# Proiect_TSC_v41.net
KiCad netlist of a schematic drawn in EAGLE
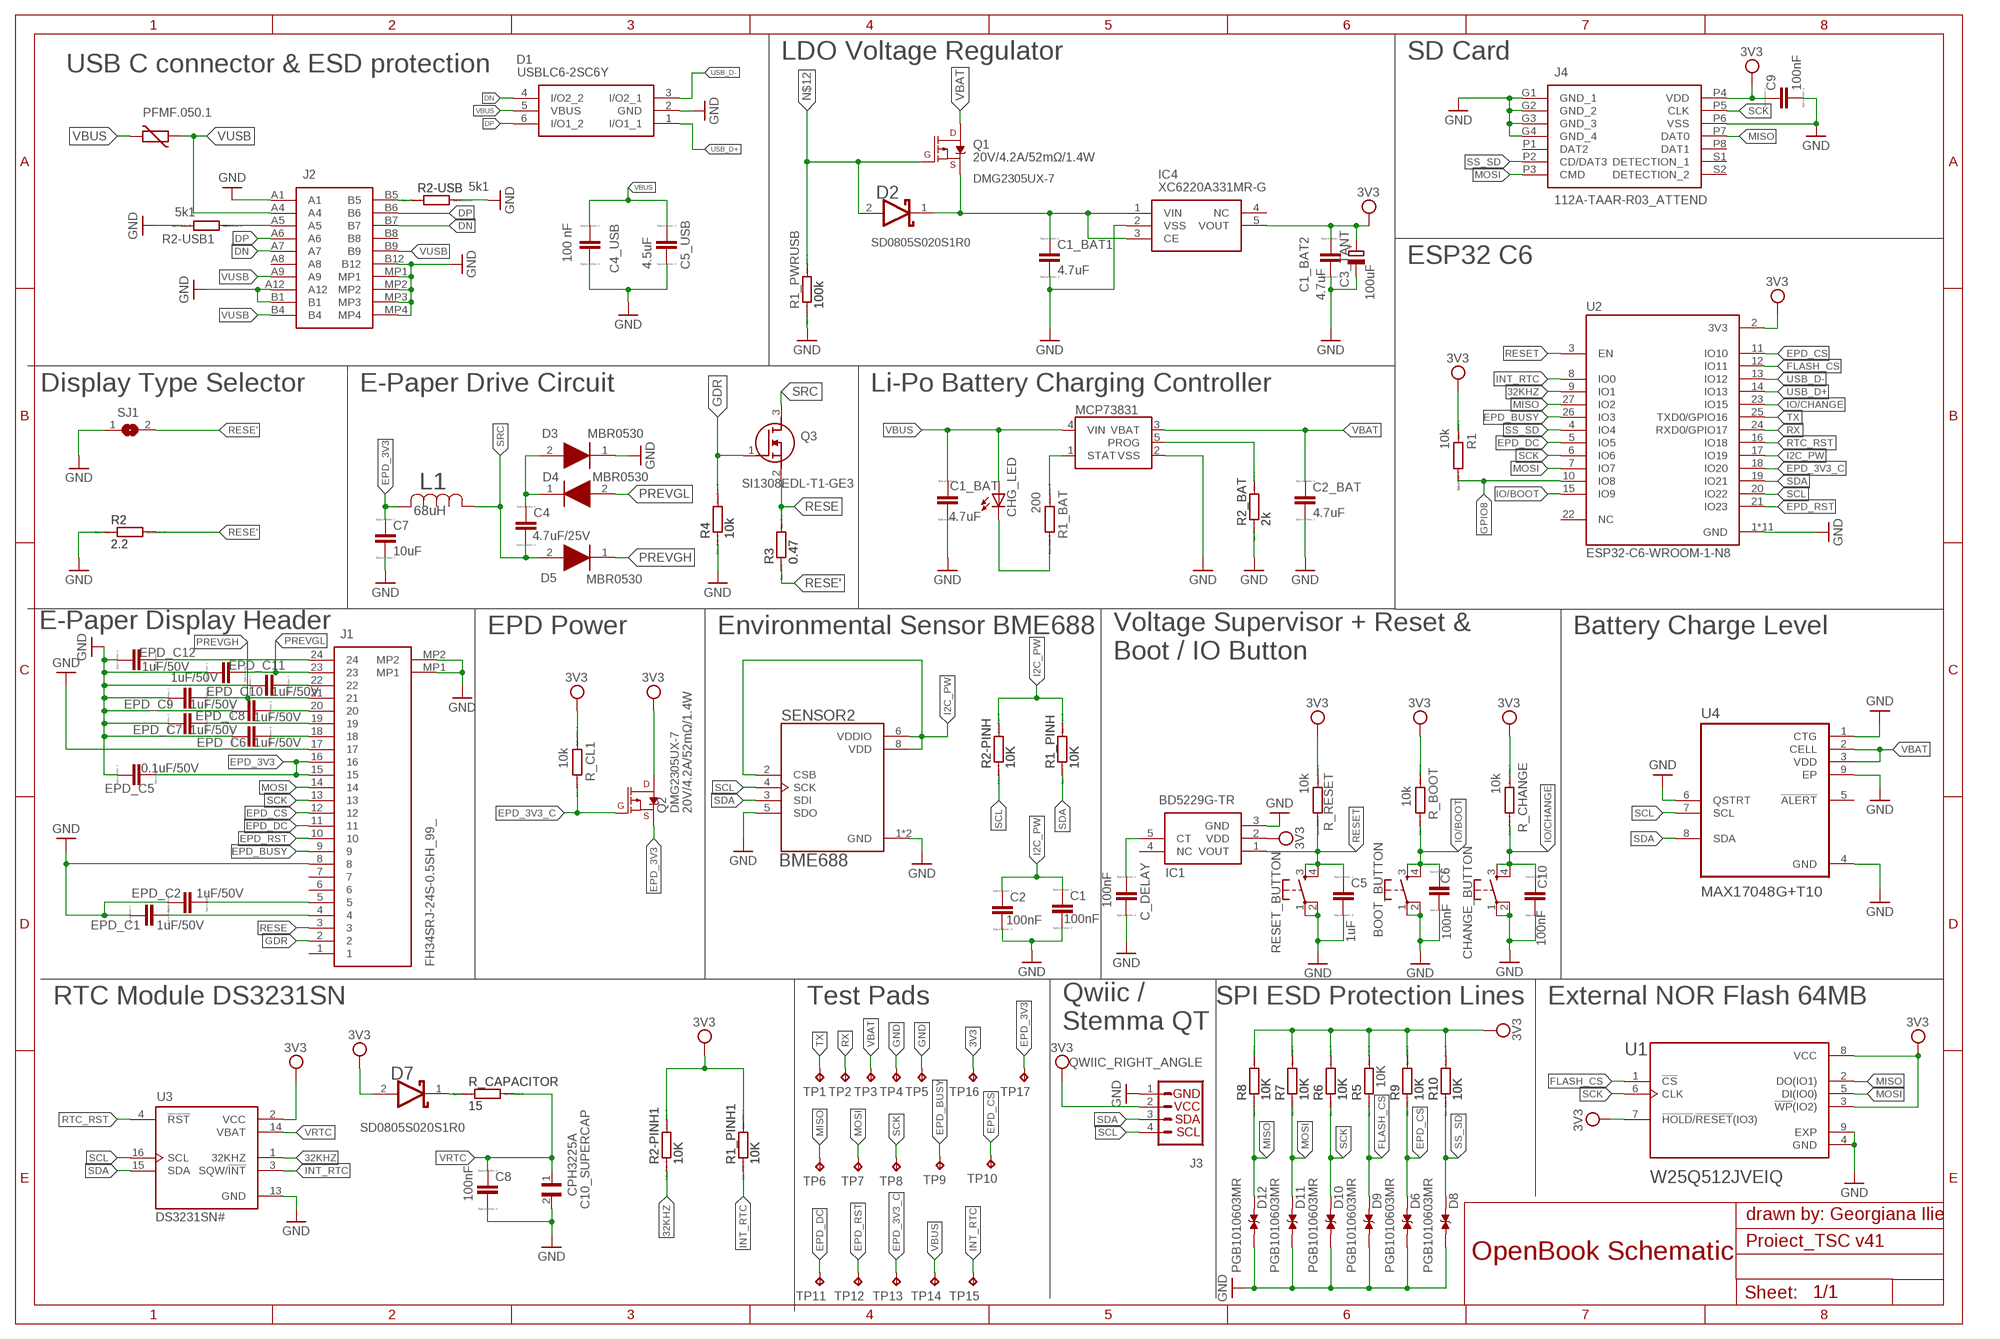
[diagram p0: schematic, sheet 1]

(export (version "E")
  (design (tool "Eeschema 10.0.6"))
  (components
    (comp (ref "BOOT_BUTTON")
      (value "BUTTON_CUSYOMV1")
      (footprint "eagle-import:MYBUTTON")
      (libsource (lib "eagle-import") (part "BUTTON_CUSYOMV1"))
    )
    (comp (ref "C1")
      (value "100nF")
      (footprint "eagle-import:EAGLE-LTSPICE_C0402")
      (libsource (lib "eagle-import") (part "EAGLE-LTSPICE_CC0402"))
    )
    (comp (ref "C1_BAT")
      (value "4.7uF")
      (footprint "eagle-import:EAGLE-LTSPICE_C0402")
      (libsource (lib "eagle-import") (part "EAGLE-LTSPICE_CC0402"))
    )
    (comp (ref "C1_BAT1")
      (value "4.7uF")
      (footprint "eagle-import:ESP32_WROVER_EAGLE-LTSPICE_C0402")
      (libsource (lib "eagle-import") (part "ESP32_WROVER_EAGLE-LTSPICE_CC0402"))
    )
    (comp (ref "C1_BAT2")
      (value "4.7uF")
      (footprint "eagle-import:ESP32_WROVER_EAGLE-LTSPICE_C0402")
      (libsource (lib "eagle-import") (part "ESP32_WROVER_EAGLE-LTSPICE_CC0402"))
    )
    (comp (ref "C2")
      (value "100nF")
      (footprint "eagle-import:EAGLE-LTSPICE_C0402")
      (libsource (lib "eagle-import") (part "EAGLE-LTSPICE_CC0402"))
    )
    (comp (ref "C2_BAT")
      (value "4.7uF")
      (footprint "eagle-import:EAGLE-LTSPICE_C0402")
      (libsource (lib "eagle-import") (part "EAGLE-LTSPICE_CC0402"))
    )
    (comp (ref "C3_TANT")
      (value "100uF")
      (footprint "eagle-import:RCL_CT3528")
      (libsource (lib "eagle-import") (part "RCL_CPOL-EUCT3528"))
    )
    (comp (ref "C4")
      (value "4.7uF/25V")
      (footprint "eagle-import:EAGLE-LTSPICE_C0402")
      (libsource (lib "eagle-import") (part "EAGLE-LTSPICE_CC0402"))
    )
    (comp (ref "C4_USB")
      (value "100 nF")
      (footprint "eagle-import:ESP32_WROVER_EAGLE-LTSPICE_C0402")
      (libsource (lib "eagle-import") (part "ESP32_WROVER_EAGLE-LTSPICE_CC0402"))
    )
    (comp (ref "C5")
      (value "1uF")
      (footprint "eagle-import:EAGLE-LTSPICE_C0402")
      (libsource (lib "eagle-import") (part "EAGLE-LTSPICE_CC0402"))
    )
    (comp (ref "C5_USB")
      (value "4.5uF")
      (footprint "eagle-import:ESP32_WROVER_EAGLE-LTSPICE_C0402")
      (libsource (lib "eagle-import") (part "ESP32_WROVER_EAGLE-LTSPICE_CC0402"))
    )
    (comp (ref "C6")
      (value "100nF")
      (footprint "eagle-import:EAGLE-LTSPICE_C0402")
      (libsource (lib "eagle-import") (part "EAGLE-LTSPICE_CC0402"))
    )
    (comp (ref "C7")
      (value "10uF")
      (footprint "eagle-import:EAGLE-LTSPICE_C0402")
      (libsource (lib "eagle-import") (part "EAGLE-LTSPICE_CC0402"))
    )
    (comp (ref "C8")
      (value "100nF")
      (footprint "eagle-import:EAGLE-LTSPICE_C0402")
      (libsource (lib "eagle-import") (part "EAGLE-LTSPICE_CC0402"))
    )
    (comp (ref "C9")
      (value "100nF")
      (footprint "eagle-import:EAGLE-LTSPICE_C0402")
      (libsource (lib "eagle-import") (part "EAGLE-LTSPICE_CC0402"))
    )
    (comp (ref "C10")
      (value "100nF")
      (footprint "eagle-import:EAGLE-LTSPICE_C0402")
      (libsource (lib "eagle-import") (part "EAGLE-LTSPICE_CC0402"))
    )
    (comp (ref "C10_SUPERCAP")
      (value "CPH3225A")
      (footprint "eagle-import:CAPCP3225X100N")
      (fields (field (name "MF") "Seiko Instruments"))
      (libsource (lib "eagle-import") (part "CPH3225A"))
    )
    (comp (ref "CHANGE_BUTTON")
      (value "BUTTON_CUSYOMV1")
      (footprint "eagle-import:MYBUTTON")
      (libsource (lib "eagle-import") (part "BUTTON_CUSYOMV1"))
    )
    (comp (ref "CHG_LED")
      (value "ADAFRUIT_LEDCHIP-LED0603")
      (footprint "eagle-import:ADAFRUIT_CHIP-LED0603")
      (libsource (lib "eagle-import") (part "ADAFRUIT_LEDCHIP-LED0603"))
    )
    (comp (ref "C_DELAY")
      (value "100nF")
      (footprint "eagle-import:EAGLE-LTSPICE_C0402")
      (libsource (lib "eagle-import") (part "EAGLE-LTSPICE_CC0402"))
    )
    (comp (ref "D1")
      (value "USBLC6-2SC6Y")
      (footprint "eagle-import:SOT95P280X145-6N")
      (fields (field (name "MF") "STMicroelectronics"))
      (libsource (lib "eagle-import") (part "USBLC6-2SC6Y"))
    )
    (comp (ref "D2")
      (value "ESP32_WROVER_AVX---SD0805S020S1R0_AVX_SD0805S020S1R0_0_0AVX_SD0805S020S1R0_0_0")
      (footprint "eagle-import:ESP32_WROVER_AVX---SD0805S020S1R0_AVX_SD0805S020S1R0_0")
      (fields
        (field (name "DIGIKEY_PART_NUMBER") "478-7800-1-ND")
        (field (name "MF") "AVX")
        (field (name "MOUSER_PART_NUMBER") "581-SD0805S020S1R0")
      )
      (libsource (lib "eagle-import") (part "ESP32_WROVER_AVX---SD0805S020S1R0_AVX_SD0805S020S1R0_0_0AVX_SD0805S020S1R0_0_0"))
    )
    (comp (ref "D3")
      (value "MBR0530")
      (footprint "eagle-import:SOD3716X135N")
      (fields (field (name "MF") "ON Semiconductor"))
      (libsource (lib "eagle-import") (part "MBR0530"))
    )
    (comp (ref "D4")
      (value "MBR0530")
      (footprint "eagle-import:SOD3716X135N")
      (fields (field (name "MF") "ON Semiconductor"))
      (libsource (lib "eagle-import") (part "MBR0530"))
    )
    (comp (ref "D5")
      (value "MBR0530")
      (footprint "eagle-import:SOD3716X135N")
      (fields (field (name "MF") "ON Semiconductor"))
      (libsource (lib "eagle-import") (part "MBR0530"))
    )
    (comp (ref "D6")
      (value "PGB1010603MR")
      (footprint "eagle-import:DIOC1608X36N")
      (fields (field (name "MF") "Littelfuse Inc."))
      (libsource (lib "eagle-import") (part "PGB1010603MR"))
    )
    (comp (ref "D7")
      (value "ESP32_WROVER_AVX---SD0805S020S1R0_AVX_SD0805S020S1R0_0_0AVX_SD0805S020S1R0_0_0")
      (footprint "eagle-import:ESP32_WROVER_AVX---SD0805S020S1R0_AVX_SD0805S020S1R0_0")
      (fields
        (field (name "DIGIKEY_PART_NUMBER") "478-7800-1-ND")
        (field (name "MF") "AVX")
        (field (name "MOUSER_PART_NUMBER") "581-SD0805S020S1R0")
      )
      (libsource (lib "eagle-import") (part "ESP32_WROVER_AVX---SD0805S020S1R0_AVX_SD0805S020S1R0_0_0AVX_SD0805S020S1R0_0_0"))
    )
    (comp (ref "D8")
      (value "PGB1010603MR")
      (footprint "eagle-import:DIOC1608X36N")
      (fields (field (name "MF") "Littelfuse Inc."))
      (libsource (lib "eagle-import") (part "PGB1010603MR"))
    )
    (comp (ref "D9")
      (value "PGB1010603MR")
      (footprint "eagle-import:DIOC1608X36N")
      (fields (field (name "MF") "Littelfuse Inc."))
      (libsource (lib "eagle-import") (part "PGB1010603MR"))
    )
    (comp (ref "D10")
      (value "PGB1010603MR")
      (footprint "eagle-import:DIOC1608X36N")
      (fields (field (name "MF") "Littelfuse Inc."))
      (libsource (lib "eagle-import") (part "PGB1010603MR"))
    )
    (comp (ref "D11")
      (value "PGB1010603MR")
      (footprint "eagle-import:DIOC1608X36N")
      (fields (field (name "MF") "Littelfuse Inc."))
      (libsource (lib "eagle-import") (part "PGB1010603MR"))
    )
    (comp (ref "D12")
      (value "PGB1010603MR")
      (footprint "eagle-import:DIOC1608X36N")
      (fields (field (name "MF") "Littelfuse Inc."))
      (libsource (lib "eagle-import") (part "PGB1010603MR"))
    )
    (comp (ref "EPD_C1")
      (value "1uF/50V")
      (footprint "eagle-import:EAGLE-LTSPICE_C0402")
      (libsource (lib "eagle-import") (part "EAGLE-LTSPICE_CC0402"))
    )
    (comp (ref "EPD_C2")
      (value "1uF/50V")
      (footprint "eagle-import:EAGLE-LTSPICE_C0402")
      (libsource (lib "eagle-import") (part "EAGLE-LTSPICE_CC0402"))
    )
    (comp (ref "EPD_C5")
      (value "0.1uF/50V")
      (footprint "eagle-import:EAGLE-LTSPICE_C0402")
      (libsource (lib "eagle-import") (part "EAGLE-LTSPICE_CC0402"))
    )
    (comp (ref "EPD_C6")
      (value "1uF/50V")
      (footprint "eagle-import:EAGLE-LTSPICE_C0402")
      (libsource (lib "eagle-import") (part "EAGLE-LTSPICE_CC0402"))
    )
    (comp (ref "EPD_C7")
      (value "1uF/50V")
      (footprint "eagle-import:EAGLE-LTSPICE_C0402")
      (libsource (lib "eagle-import") (part "EAGLE-LTSPICE_CC0402"))
    )
    (comp (ref "EPD_C8")
      (value "1uF/50V")
      (footprint "eagle-import:EAGLE-LTSPICE_C0402")
      (libsource (lib "eagle-import") (part "EAGLE-LTSPICE_CC0402"))
    )
    (comp (ref "EPD_C9")
      (value "1uF/50V")
      (footprint "eagle-import:EAGLE-LTSPICE_C0402")
      (libsource (lib "eagle-import") (part "EAGLE-LTSPICE_CC0402"))
    )
    (comp (ref "EPD_C10")
      (value "1uF/50V")
      (footprint "eagle-import:EAGLE-LTSPICE_C0402")
      (libsource (lib "eagle-import") (part "EAGLE-LTSPICE_CC0402"))
    )
    (comp (ref "EPD_C11")
      (value "1uF/50V")
      (footprint "eagle-import:EAGLE-LTSPICE_C0402")
      (libsource (lib "eagle-import") (part "EAGLE-LTSPICE_CC0402"))
    )
    (comp (ref "EPD_C12")
      (value "1uF/50V")
      (footprint "eagle-import:EAGLE-LTSPICE_C0402")
      (libsource (lib "eagle-import") (part "EAGLE-LTSPICE_CC0402"))
    )
    (comp (ref "IC1")
      (value "BD5229G-TR")
      (footprint "eagle-import:SOT95P280X125-5N")
      (fields (field (name "MOUSER_PART_NUMBER") "755-BD5229G-TR"))
      (libsource (lib "eagle-import") (part "BD5229G-TR"))
    )
    (comp (ref "IC4")
      (value "XC6220A331MR-G")
      (footprint "eagle-import:SOT95P280X120-5N")
      (fields (field (name "MOUSER_PART_NUMBER") "865-XC6220A331MR-G"))
      (libsource (lib "eagle-import") (part "XC6220A331MR-G"))
    )
    (comp (ref "J1")
      (value "FH34SRJ-24S-0.5SH_99_")
      (footprint "eagle-import:FH34SRJ24S05SH99")
      (fields
        (field (name "MANUFACTURER_PART_NUMBER") "FH34SRJ-24S-0.5SH(99)")
        (field (name "MOUSER_PART_NUMBER") "798-FH34SRJ24S05SH99")
      )
      (libsource (lib "eagle-import") (part "FH34SRJ-24S-0.5SH_99_"))
    )
    (comp (ref "J2")
      (value "SAMACSYS_PARTS_USB4110-GF-A")
      (footprint "eagle-import:SAMACSYS_PARTS_USB4110GFA")
      (fields
        (field (name "MANUFACTURER_PART_NUMBER") "USB4110-GF-A")
        (field (name "MOUSER_PART_NUMBER") "640-USB4110-GF-A")
      )
      (libsource (lib "eagle-import") (part "SAMACSYS_PARTS_USB4110-GF-A"))
    )
    (comp (ref "J3")
      (value "QWIIC_RIGHT_ANGLE")
      (footprint "eagle-import:JST04_1MM_RA")
      (libsource (lib "eagle-import") (part "QWIIC_CONNECTORJS-1MM"))
    )
    (comp (ref "J4")
      (value "112A-TAAR-R03_ATTEND")
      (footprint "eagle-import:112ATAARR03ATTEND")
      (fields (field (name "MANUFACTURER_PART_NUMBER") "112A-TAAR-R03 ATTEND"))
      (libsource (lib "eagle-import") (part "112A-TAAR-R03_ATTEND"))
    )
    (comp (ref "L1")
      (value "68uH")
      (footprint "eagle-import:IND_4828-WE-TPC_WRE")
      (fields
        (field (name "MANUFACTURER_PART_NUMBER") "744043680")
        (field (name "COPYRIGHT") "Copyright (C) 2024 Ultra Librarian. All rights reserved.")
      )
      (libsource (lib "eagle-import") (part "744043680IND_4828-WE-TPC_WRE"))
    )
    (comp (ref "MCP73831")
      (value "ESP32_WROVER_SPARKFUN-IC-POWER_MCP73831")
      (footprint "eagle-import:ESP32_WROVER_SPARKFUN-IC-POWER_SOT23-5")
      (libsource (lib "eagle-import") (part "ESP32_WROVER_SPARKFUN-IC-POWER_MCP73831"))
    )
    (comp (ref "PFMF.050.1")
      (value "ESP32C6_VARISTORCN1812")
      (footprint "eagle-import:ESP32C6_VARISTOR_CT_CN1812")
      (libsource (lib "eagle-import") (part "ESP32C6_VARISTORCN1812"))
    )
    (comp (ref "Q1")
      (value "20V/4.2A/52mΩ/1.4W")
      (footprint "eagle-import:ESP32_WROVER_SPARKFUN-DISCRETESEMI_SOT23-3")
      (libsource (lib "eagle-import") (part "ESP32_WROVER_SPARKFUN-DISCRETESEMI_MOSFET_PCH-DMG2305UX-7"))
    )
    (comp (ref "Q2")
      (value "20V/4.2A/52mΩ/1.4W")
      (footprint "eagle-import:ESP32_WROVER_SPARKFUN-DISCRETESEMI_SOT23-3")
      (libsource (lib "eagle-import") (part "ESP32_WROVER_SPARKFUN-DISCRETESEMI_MOSFET_PCH-DMG2305UX-7"))
    )
    (comp (ref "Q3")
      (value "SI1308EDL-T1-GE3")
      (footprint "eagle-import:SOT65P210X110-3N")
      (fields (field (name "MF") "Vishay Siliconix"))
      (libsource (lib "eagle-import") (part "SI1308EDL-T1-GE3"))
    )
    (comp (ref "R1")
      (value "10k")
      (footprint "eagle-import:ESP32_WROVER_EAGLE-LTSPICE_R0402")
      (libsource (lib "eagle-import") (part "ESP32_WROVER_EAGLE-LTSPICE_RR0402"))
    )
    (comp (ref "R1_BAT")
      (value "200")
      (footprint "eagle-import:ESP32_WROVER_EAGLE-LTSPICE_R0402")
      (libsource (lib "eagle-import") (part "ESP32_WROVER_EAGLE-LTSPICE_RR0402"))
    )
    (comp (ref "R1_PINH")
      (value "10K")
      (footprint "eagle-import:ESP32_WROVER_EAGLE-LTSPICE_R0402")
      (libsource (lib "eagle-import") (part "ESP32_WROVER_EAGLE-LTSPICE_RR0402"))
    )
    (comp (ref "R1_PINH1")
      (value "10K")
      (footprint "eagle-import:ESP32_WROVER_EAGLE-LTSPICE_R0402")
      (libsource (lib "eagle-import") (part "ESP32_WROVER_EAGLE-LTSPICE_RR0402"))
    )
    (comp (ref "R1_PWRUSB")
      (value "100k")
      (footprint "eagle-import:ESP32_WROVER_EAGLE-LTSPICE_R0402")
      (libsource (lib "eagle-import") (part "ESP32_WROVER_EAGLE-LTSPICE_RR0402"))
    )
    (comp (ref "R2")
      (value "2.2")
      (footprint "eagle-import:ESP32_WROVER_EAGLE-LTSPICE_R0402")
      (libsource (lib "eagle-import") (part "ESP32_WROVER_EAGLE-LTSPICE_RR0402"))
    )
    (comp (ref "R2-PINH")
      (value "10K")
      (footprint "eagle-import:ESP32_WROVER_EAGLE-LTSPICE_R0402")
      (libsource (lib "eagle-import") (part "ESP32_WROVER_EAGLE-LTSPICE_RR0402"))
    )
    (comp (ref "R2-PINH1")
      (value "10K")
      (footprint "eagle-import:ESP32_WROVER_EAGLE-LTSPICE_R0402")
      (libsource (lib "eagle-import") (part "ESP32_WROVER_EAGLE-LTSPICE_RR0402"))
    )
    (comp (ref "R2-USB")
      (value "5k1")
      (footprint "eagle-import:ESP32_WROVER_EAGLE-LTSPICE_R0402")
      (libsource (lib "eagle-import") (part "ESP32_WROVER_EAGLE-LTSPICE_RR0402"))
    )
    (comp (ref "R2-USB1")
      (value "5k1")
      (footprint "eagle-import:ESP32_WROVER_EAGLE-LTSPICE_R0402")
      (libsource (lib "eagle-import") (part "ESP32_WROVER_EAGLE-LTSPICE_RR0402"))
    )
    (comp (ref "R2_BAT")
      (value "2k")
      (footprint "eagle-import:ESP32_WROVER_EAGLE-LTSPICE_R0402")
      (libsource (lib "eagle-import") (part "ESP32_WROVER_EAGLE-LTSPICE_RR0402"))
    )
    (comp (ref "R3")
      (value "0.47")
      (footprint "eagle-import:ESP32_WROVER_EAGLE-LTSPICE_R0402")
      (libsource (lib "eagle-import") (part "ESP32_WROVER_EAGLE-LTSPICE_RR0402"))
    )
    (comp (ref "R4")
      (value "10k")
      (footprint "eagle-import:ESP32_WROVER_EAGLE-LTSPICE_R0402")
      (libsource (lib "eagle-import") (part "ESP32_WROVER_EAGLE-LTSPICE_RR0402"))
    )
    (comp (ref "R5")
      (value "10K")
      (footprint "eagle-import:ESP32_WROVER_EAGLE-LTSPICE_R0402")
      (libsource (lib "eagle-import") (part "ESP32_WROVER_EAGLE-LTSPICE_RR0402"))
    )
    (comp (ref "R6")
      (value "10K")
      (footprint "eagle-import:ESP32_WROVER_EAGLE-LTSPICE_R0402")
      (libsource (lib "eagle-import") (part "ESP32_WROVER_EAGLE-LTSPICE_RR0402"))
    )
    (comp (ref "R7")
      (value "10K")
      (footprint "eagle-import:ESP32_WROVER_EAGLE-LTSPICE_R0402")
      (libsource (lib "eagle-import") (part "ESP32_WROVER_EAGLE-LTSPICE_RR0402"))
    )
    (comp (ref "R8")
      (value "10K")
      (footprint "eagle-import:ESP32_WROVER_EAGLE-LTSPICE_R0402")
      (libsource (lib "eagle-import") (part "ESP32_WROVER_EAGLE-LTSPICE_RR0402"))
    )
    (comp (ref "R9")
      (value "10K")
      (footprint "eagle-import:ESP32_WROVER_EAGLE-LTSPICE_R0402")
      (libsource (lib "eagle-import") (part "ESP32_WROVER_EAGLE-LTSPICE_RR0402"))
    )
    (comp (ref "R10")
      (value "10K")
      (footprint "eagle-import:ESP32_WROVER_EAGLE-LTSPICE_R0402")
      (libsource (lib "eagle-import") (part "ESP32_WROVER_EAGLE-LTSPICE_RR0402"))
    )
    (comp (ref "RESET_BUTTON")
      (value "BUTTON_CUSYOMV1")
      (footprint "eagle-import:MYBUTTON")
      (libsource (lib "eagle-import") (part "BUTTON_CUSYOMV1"))
    )
    (comp (ref "R_BOOT")
      (value "10k")
      (footprint "eagle-import:ESP32_WROVER_EAGLE-LTSPICE_R0402")
      (libsource (lib "eagle-import") (part "ESP32_WROVER_EAGLE-LTSPICE_RR0402"))
    )
    (comp (ref "R_CAPACITOR")
      (value "15")
      (footprint "eagle-import:ESP32_WROVER_EAGLE-LTSPICE_R0402")
      (libsource (lib "eagle-import") (part "ESP32_WROVER_EAGLE-LTSPICE_RR0402"))
    )
    (comp (ref "R_CHANGE")
      (value "10k")
      (footprint "eagle-import:ESP32_WROVER_EAGLE-LTSPICE_R0402")
      (libsource (lib "eagle-import") (part "ESP32_WROVER_EAGLE-LTSPICE_RR0402"))
    )
    (comp (ref "R_CL1")
      (value "10k")
      (footprint "eagle-import:ESP32_WROVER_EAGLE-LTSPICE_R0402")
      (libsource (lib "eagle-import") (part "ESP32_WROVER_EAGLE-LTSPICE_RR0402"))
    )
    (comp (ref "R_RESET")
      (value "10k")
      (footprint "eagle-import:ESP32_WROVER_EAGLE-LTSPICE_R0402")
      (libsource (lib "eagle-import") (part "ESP32_WROVER_EAGLE-LTSPICE_RR0402"))
    )
    (comp (ref "SENSOR2")
      (value "ESP32_WROVER_BME680_BME680")
      (footprint "eagle-import:ESP32_WROVER_BME680_PSON80P300X300X100-8N")
      (fields (field (name "MF") "Bosch Sensortec") (field (name "MP") "BME680"))
      (libsource (lib "eagle-import") (part "ESP32_WROVER_BME680_BME680"))
    )
    (comp (ref "SJ1") (value "SJ") (footprint "eagle-import:SJ") (libsource (lib "eagle-import") (part "SJ")))
    (comp (ref "TP1")
      (value "TPTP20R")
      (footprint "eagle-import:TP20R")
      (libsource (lib "eagle-import") (part "TPTP20R"))
    )
    (comp (ref "TP2")
      (value "TPTP20R")
      (footprint "eagle-import:TP20R")
      (libsource (lib "eagle-import") (part "TPTP20R"))
    )
    (comp (ref "TP3")
      (value "TPTP20R")
      (footprint "eagle-import:TP20R")
      (libsource (lib "eagle-import") (part "TPTP20R"))
    )
    (comp (ref "TP4")
      (value "TPTP20R")
      (footprint "eagle-import:TP20R")
      (libsource (lib "eagle-import") (part "TPTP20R"))
    )
    (comp (ref "TP5")
      (value "TPTP20R")
      (footprint "eagle-import:TP20R")
      (libsource (lib "eagle-import") (part "TPTP20R"))
    )
    (comp (ref "TP6")
      (value "TPTP20R")
      (footprint "eagle-import:TP20R")
      (libsource (lib "eagle-import") (part "TPTP20R"))
    )
    (comp (ref "TP7")
      (value "TPTP20R")
      (footprint "eagle-import:TP20R")
      (libsource (lib "eagle-import") (part "TPTP20R"))
    )
    (comp (ref "TP8")
      (value "TPTP20R")
      (footprint "eagle-import:TP20R")
      (libsource (lib "eagle-import") (part "TPTP20R"))
    )
    (comp (ref "TP9")
      (value "TPTP20R")
      (footprint "eagle-import:TP20R")
      (libsource (lib "eagle-import") (part "TPTP20R"))
    )
    (comp (ref "TP10")
      (value "TPTP20R")
      (footprint "eagle-import:TP20R")
      (libsource (lib "eagle-import") (part "TPTP20R"))
    )
    (comp (ref "TP11")
      (value "TPTP20R")
      (footprint "eagle-import:TP20R")
      (libsource (lib "eagle-import") (part "TPTP20R"))
    )
    (comp (ref "TP12")
      (value "TPTP20R")
      (footprint "eagle-import:TP20R")
      (libsource (lib "eagle-import") (part "TPTP20R"))
    )
    (comp (ref "TP13")
      (value "TPTP20R")
      (footprint "eagle-import:TP20R")
      (libsource (lib "eagle-import") (part "TPTP20R"))
    )
    (comp (ref "TP14")
      (value "TPTP20R")
      (footprint "eagle-import:TP20R")
      (libsource (lib "eagle-import") (part "TPTP20R"))
    )
    (comp (ref "TP15")
      (value "TPTP20R")
      (footprint "eagle-import:TP20R")
      (libsource (lib "eagle-import") (part "TPTP20R"))
    )
    (comp (ref "TP16")
      (value "TPTP20R")
      (footprint "eagle-import:TP20R")
      (libsource (lib "eagle-import") (part "TPTP20R"))
    )
    (comp (ref "TP17")
      (value "TPTP20R")
      (footprint "eagle-import:TP20R")
      (libsource (lib "eagle-import") (part "TPTP20R"))
    )
    (comp (ref "U1")
      (value "W25Q512JVEIQ")
      (footprint "eagle-import:SON127P600X800X80-9N")
      (fields (field (name "MF") "Winbond Electronics"))
      (libsource (lib "eagle-import") (part "W25Q512JVEIQ"))
    )
    (comp (ref "U2")
      (value "ESP32-C6-WROOM-1-N8")
      (footprint "eagle-import:XCVR_ESP32-C6-WROOM-1-N8")
      (fields (field (name "MF") "Espressif Systems"))
      (libsource (lib "eagle-import") (part "ESP32-C6-WROOM-1-N8"))
    )
    (comp (ref "U3")
      (value "DS3231SN#")
      (footprint "eagle-import:SOIC127P1032X265-16N")
      (fields (field (name "MF") "Analog Devices"))
      (libsource (lib "eagle-import") (part "DS3231SN#"))
    )
    (comp (ref "U4")
      (value "MAX17048G+T10")
      (footprint "eagle-import:SON50P200X200X80-9N")
      (fields (field (name "MF") "Analog Devices"))
      (libsource (lib "eagle-import") (part "MAX17048G+T10"))
    )
  )
  (nets
    (net (code "1") (name "3V3") (class "Default")
      (node (ref "C1_BAT2") (pin "1") (pinfunction "1_1") (pintype "passive"))
      (node (ref "C3_TANT") (pin "+") (pinfunction "+_+") (pintype "passive"))
      (node (ref "C9") (pin "1") (pinfunction "1_1") (pintype "passive"))
      (node (ref "D7") (pin "2") (pinfunction "ANODE_2") (pintype "bidirectional"))
      (node (ref "IC1") (pin "2") (pinfunction "VDD_2") (pintype "bidirectional"))
      (node (ref "IC4") (pin "5") (pinfunction "VOUT_5") (pintype "bidirectional"))
      (node (ref "J3") (pin "2") (pinfunction "2_2") (pintype "power_in"))
      (node (ref "J4") (pin "P4") (pinfunction "VDD_P4") (pintype "bidirectional"))
      (node (ref "Q2") (pin "3") (pinfunction "D_3") (pintype "bidirectional"))
      (node (ref "R1") (pin "2") (pinfunction "2_2") (pintype "passive"))
      (node (ref "R10") (pin "2") (pinfunction "2_2") (pintype "passive"))
      (node (ref "R1_PINH1") (pin "2") (pinfunction "2_2") (pintype "passive"))
      (node (ref "R2-PINH1") (pin "2") (pinfunction "2_2") (pintype "passive"))
      (node (ref "R5") (pin "2") (pinfunction "2_2") (pintype "passive"))
      (node (ref "R6") (pin "2") (pinfunction "2_2") (pintype "passive"))
      (node (ref "R7") (pin "2") (pinfunction "2_2") (pintype "passive"))
      (node (ref "R8") (pin "2") (pinfunction "2_2") (pintype "passive"))
      (node (ref "R9") (pin "2") (pinfunction "2_2") (pintype "passive"))
      (node (ref "R_BOOT") (pin "2") (pinfunction "2_2") (pintype "passive"))
      (node (ref "R_CHANGE") (pin "2") (pinfunction "2_2") (pintype "passive"))
      (node (ref "R_CL1") (pin "2") (pinfunction "2_2") (pintype "passive"))
      (node (ref "R_RESET") (pin "2") (pinfunction "2_2") (pintype "passive"))
      (node (ref "TP16") (pin "TP") (pinfunction "TP_TP") (pintype "input"))
      (node (ref "U1") (pin "3") (pinfunction "~{WP}(IO2)_3") (pintype "bidirectional"))
      (node (ref "U1") (pin "7") (pinfunction "~{HOLD}/~{RESET}(IO3)_7") (pintype "bidirectional"))
      (node (ref "U1") (pin "8") (pinfunction "VCC_8") (pintype "power_in"))
      (node (ref "U2") (pin "2") (pinfunction "3V3_2") (pintype "power_in"))
      (node (ref "U3") (pin "2") (pinfunction "VCC_2") (pintype "power_in"))
    )
    (net (code "2") (name "32KHZ") (class "Default")
      (node (ref "R2-PINH1") (pin "1") (pinfunction "1_1") (pintype "passive"))
      (node (ref "U2") (pin "9") (pinfunction "IO1_9") (pintype "bidirectional"))
      (node (ref "U3") (pin "1") (pinfunction "32KHZ_1") (pintype "output"))
    )
    (net (code "3") (name "DN") (class "Default")
      (node (ref "D1") (pin "4") (pinfunction "I/O2_2_4") (pintype "bidirectional"))
      (node (ref "J2") (pin "A7") (pinfunction "A7_A7") (pintype "bidirectional"))
      (node (ref "J2") (pin "B7") (pinfunction "B7_B7") (pintype "bidirectional"))
    )
    (net (code "4") (name "DP") (class "Default")
      (node (ref "D1") (pin "6") (pinfunction "I/O1_2_6") (pintype "bidirectional"))
      (node (ref "J2") (pin "A6") (pinfunction "A6_A6") (pintype "bidirectional"))
      (node (ref "J2") (pin "B6") (pinfunction "B6_B6") (pintype "bidirectional"))
    )
    (net (code "5") (name "EPD_3V3") (class "Default")
      (node (ref "C7") (pin "1") (pinfunction "1_1") (pintype "passive"))
      (node (ref "EPD_C5") (pin "2") (pinfunction "2_2") (pintype "passive"))
      (node (ref "J1") (pin "15") (pinfunction "15_15") (pintype "bidirectional"))
      (node (ref "J1") (pin "16") (pinfunction "16_16") (pintype "bidirectional"))
      (node (ref "L1") (pin "2") (pinfunction "2_2") (pintype "passive"))
      (node (ref "Q2") (pin "2") (pinfunction "S_2") (pintype "bidirectional"))
      (node (ref "TP17") (pin "TP") (pinfunction "TP_TP") (pintype "input"))
    )
    (net (code "6") (name "EPD_3V3_C") (class "Default")
      (node (ref "Q2") (pin "1") (pinfunction "G_1") (pintype "bidirectional"))
      (node (ref "R_CL1") (pin "1") (pinfunction "1_1") (pintype "passive"))
      (node (ref "TP13") (pin "TP") (pinfunction "TP_TP") (pintype "input"))
      (node (ref "U2") (pin "18") (pinfunction "IO20_18") (pintype "bidirectional"))
    )
    (net (code "7") (name "EPD_BUSY") (class "Default")
      (node (ref "J1") (pin "9") (pinfunction "9_9") (pintype "bidirectional"))
      (node (ref "TP9") (pin "TP") (pinfunction "TP_TP") (pintype "input"))
      (node (ref "U2") (pin "26") (pinfunction "IO3_26") (pintype "bidirectional"))
    )
    (net (code "8") (name "EPD_CS") (class "Default")
      (node (ref "D6") (pin "2") (pinfunction "2_2") (pintype "passive"))
      (node (ref "J1") (pin "12") (pinfunction "12_12") (pintype "bidirectional"))
      (node (ref "R9") (pin "1") (pinfunction "1_1") (pintype "passive"))
      (node (ref "TP10") (pin "TP") (pinfunction "TP_TP") (pintype "input"))
      (node (ref "U2") (pin "11") (pinfunction "IO10_11") (pintype "bidirectional"))
    )
    (net (code "9") (name "EPD_DC") (class "Default")
      (node (ref "J1") (pin "11") (pinfunction "11_11") (pintype "bidirectional"))
      (node (ref "TP11") (pin "TP") (pinfunction "TP_TP") (pintype "input"))
      (node (ref "U2") (pin "5") (pinfunction "IO5_5") (pintype "bidirectional"))
    )
    (net (code "10") (name "EPD_RST") (class "Default")
      (node (ref "J1") (pin "10") (pinfunction "10_10") (pintype "bidirectional"))
      (node (ref "TP12") (pin "TP") (pinfunction "TP_TP") (pintype "input"))
      (node (ref "U2") (pin "21") (pinfunction "IO23_21") (pintype "bidirectional"))
    )
    (net (code "11") (name "FLASH_CS") (class "Default")
      (node (ref "D9") (pin "2") (pinfunction "2_2") (pintype "passive"))
      (node (ref "R5") (pin "1") (pinfunction "1_1") (pintype "passive"))
      (node (ref "U1") (pin "1") (pinfunction "~{CS}_1") (pintype "input"))
      (node (ref "U2") (pin "12") (pinfunction "IO11_12") (pintype "bidirectional"))
    )
    (net (code "12") (name "GDR") (class "Default")
      (node (ref "J1") (pin "2") (pinfunction "2_2") (pintype "bidirectional"))
      (node (ref "Q3") (pin "1") (pinfunction "G_1") (pintype "bidirectional"))
      (node (ref "R4") (pin "2") (pinfunction "2_2") (pintype "passive"))
    )
    (net (code "13") (name "GND") (class "Default")
      (node (ref "BOOT_BUTTON") (pin "1") (pinfunction "1_1") (pintype "passive"))
      (node (ref "BOOT_BUTTON") (pin "2") (pinfunction "2_2") (pintype "passive"))
      (node (ref "C1") (pin "2") (pinfunction "2_2") (pintype "passive"))
      (node (ref "C10") (pin "2") (pinfunction "2_2") (pintype "passive"))
      (node (ref "C10_SUPERCAP") (pin "2") (pinfunction "2_2") (pintype "passive"))
      (node (ref "C1_BAT") (pin "2") (pinfunction "2_2") (pintype "passive"))
      (node (ref "C1_BAT1") (pin "2") (pinfunction "2_2") (pintype "passive"))
      (node (ref "C1_BAT2") (pin "2") (pinfunction "2_2") (pintype "passive"))
      (node (ref "C2") (pin "2") (pinfunction "2_2") (pintype "passive"))
      (node (ref "C2_BAT") (pin "2") (pinfunction "2_2") (pintype "passive"))
      (node (ref "C3_TANT") (pin "-") (pinfunction "-_-") (pintype "passive"))
      (node (ref "C4_USB") (pin "2") (pinfunction "2_2") (pintype "passive"))
      (node (ref "C5") (pin "2") (pinfunction "2_2") (pintype "passive"))
      (node (ref "C5_USB") (pin "2") (pinfunction "2_2") (pintype "passive"))
      (node (ref "C6") (pin "2") (pinfunction "2_2") (pintype "passive"))
      (node (ref "C7") (pin "2") (pinfunction "2_2") (pintype "passive"))
      (node (ref "C8") (pin "2") (pinfunction "2_2") (pintype "passive"))
      (node (ref "C9") (pin "2") (pinfunction "2_2") (pintype "passive"))
      (node (ref "CHANGE_BUTTON") (pin "1") (pinfunction "1_1") (pintype "passive"))
      (node (ref "CHANGE_BUTTON") (pin "2") (pinfunction "2_2") (pintype "passive"))
      (node (ref "C_DELAY") (pin "2") (pinfunction "2_2") (pintype "passive"))
      (node (ref "D1") (pin "2") (pinfunction "GND_2") (pintype "bidirectional"))
      (node (ref "D10") (pin "1") (pinfunction "1_1") (pintype "passive"))
      (node (ref "D11") (pin "1") (pinfunction "1_1") (pintype "passive"))
      (node (ref "D12") (pin "1") (pinfunction "1_1") (pintype "passive"))
      (node (ref "D3") (pin "1") (pinfunction "K_1") (pintype "bidirectional"))
      (node (ref "D6") (pin "1") (pinfunction "1_1") (pintype "passive"))
      (node (ref "D8") (pin "1") (pinfunction "1_1") (pintype "passive"))
      (node (ref "D9") (pin "1") (pinfunction "1_1") (pintype "passive"))
      (node (ref "EPD_C1") (pin "1") (pinfunction "1_1") (pintype "passive"))
      (node (ref "EPD_C10") (pin "1") (pinfunction "1_1") (pintype "passive"))
      (node (ref "EPD_C11") (pin "1") (pinfunction "1_1") (pintype "passive"))
      (node (ref "EPD_C12") (pin "1") (pinfunction "1_1") (pintype "passive"))
      (node (ref "EPD_C2") (pin "1") (pinfunction "1_1") (pintype "passive"))
      (node (ref "EPD_C5") (pin "1") (pinfunction "1_1") (pintype "passive"))
      (node (ref "EPD_C6") (pin "1") (pinfunction "1_1") (pintype "passive"))
      (node (ref "EPD_C7") (pin "1") (pinfunction "1_1") (pintype "passive"))
      (node (ref "EPD_C8") (pin "1") (pinfunction "1_1") (pintype "passive"))
      (node (ref "EPD_C9") (pin "1") (pinfunction "1_1") (pintype "passive"))
      (node (ref "IC1") (pin "3") (pinfunction "GND_3") (pintype "bidirectional"))
      (node (ref "IC4") (pin "2") (pinfunction "VSS_2") (pintype "bidirectional"))
      (node (ref "J1") (pin "17") (pinfunction "17_17") (pintype "bidirectional"))
      (node (ref "J1") (pin "8") (pinfunction "8_8") (pintype "bidirectional"))
      (node (ref "J1") (pin "MP1") (pinfunction "MP1_MP1") (pintype "bidirectional"))
      (node (ref "J1") (pin "MP2") (pinfunction "MP2_MP2") (pintype "bidirectional"))
      (node (ref "J2") (pin "A1") (pinfunction "A1_A1") (pintype "bidirectional"))
      (node (ref "J2") (pin "A12") (pinfunction "A12_A12") (pintype "bidirectional"))
      (node (ref "J2") (pin "B1") (pinfunction "B1_B1") (pintype "bidirectional"))
      (node (ref "J2") (pin "B12") (pinfunction "B12_B12") (pintype "bidirectional"))
      (node (ref "J2") (pin "MP1") (pinfunction "MP1_MP1") (pintype "bidirectional"))
      (node (ref "J2") (pin "MP2") (pinfunction "MP2_MP2") (pintype "bidirectional"))
      (node (ref "J2") (pin "MP3") (pinfunction "MP3_MP3") (pintype "bidirectional"))
      (node (ref "J2") (pin "MP4") (pinfunction "MP4_MP4") (pintype "bidirectional"))
      (node (ref "J3") (pin "1") (pinfunction "1_1") (pintype "power_in"))
      (node (ref "J4") (pin "G1") (pinfunction "GND_1_G1") (pintype "bidirectional"))
      (node (ref "J4") (pin "G2") (pinfunction "GND_2_G2") (pintype "bidirectional"))
      (node (ref "J4") (pin "G3") (pinfunction "GND_3_G3") (pintype "bidirectional"))
      (node (ref "J4") (pin "G4") (pinfunction "GND_4_G4") (pintype "bidirectional"))
      (node (ref "J4") (pin "P6") (pinfunction "VSS_P6") (pintype "bidirectional"))
      (node (ref "MCP73831") (pin "2") (pinfunction "VSS_2") (pintype "power_in"))
      (node (ref "R1_PWRUSB") (pin "1") (pinfunction "1_1") (pintype "passive"))
      (node (ref "R2") (pin "1") (pinfunction "1_1") (pintype "passive"))
      (node (ref "R2-USB") (pin "2") (pinfunction "2_2") (pintype "passive"))
      (node (ref "R2-USB1") (pin "1") (pinfunction "1_1") (pintype "passive"))
      (node (ref "R2_BAT") (pin "1") (pinfunction "1_1") (pintype "passive"))
      (node (ref "R4") (pin "1") (pinfunction "1_1") (pintype "passive"))
      (node (ref "RESET_BUTTON") (pin "1") (pinfunction "1_1") (pintype "passive"))
      (node (ref "RESET_BUTTON") (pin "2") (pinfunction "2_2") (pintype "passive"))
      (node (ref "SENSOR2") (pin "1") (pinfunction "GND_1") (pintype "power_in"))
      (node (ref "SENSOR2") (pin "5") (pinfunction "SDO_5") (pintype "bidirectional"))
      (node (ref "SENSOR2") (pin "7") (pinfunction "GND_7") (pintype "power_in"))
      (node (ref "SJ1") (pin "1") (pinfunction "1_1") (pintype "passive"))
      (node (ref "TP4") (pin "TP") (pinfunction "TP_TP") (pintype "input"))
      (node (ref "TP5") (pin "TP") (pinfunction "TP_TP") (pintype "input"))
      (node (ref "U1") (pin "4") (pinfunction "GND_4") (pintype "power_in"))
      (node (ref "U1") (pin "9") (pinfunction "EXP_9") (pintype "passive"))
      (node (ref "U2") (pin "1") (pinfunction "GND_1") (pintype "power_in"))
      (node (ref "U2") (pin "28") (pinfunction "GND_28") (pintype "power_in"))
      (node (ref "U2") (pin "29_1") (pinfunction "GND_29_1") (pintype "power_in"))
      (node (ref "U2") (pin "29_2") (pinfunction "GND_29_2") (pintype "power_in"))
      (node (ref "U2") (pin "29_3") (pinfunction "GND_29_3") (pintype "power_in"))
      (node (ref "U2") (pin "29_4") (pinfunction "GND_29_4") (pintype "power_in"))
      (node (ref "U2") (pin "29_5") (pinfunction "GND_29_5") (pintype "power_in"))
      (node (ref "U2") (pin "29_6") (pinfunction "GND_29_6") (pintype "power_in"))
      (node (ref "U2") (pin "29_7") (pinfunction "GND_29_7") (pintype "power_in"))
      (node (ref "U2") (pin "29_8") (pinfunction "GND_29_8") (pintype "power_in"))
      (node (ref "U2") (pin "29_9") (pinfunction "GND_29_9") (pintype "power_in"))
      (node (ref "U3") (pin "13") (pinfunction "GND_13") (pintype "power_in"))
      (node (ref "U4") (pin "1") (pinfunction "CTG_1") (pintype "power_in"))
      (node (ref "U4") (pin "4") (pinfunction "GND_4") (pintype "power_in"))
      (node (ref "U4") (pin "6") (pinfunction "QSTRT_6") (pintype "input"))
      (node (ref "U4") (pin "9") (pinfunction "EP_9") (pintype "power_in"))
    )
    (net (code "14") (name "GPIO8") (class "Default")
      (node (ref "R1") (pin "1") (pinfunction "1_1") (pintype "passive"))
      (node (ref "U2") (pin "10") (pinfunction "IO8_10") (pintype "bidirectional"))
    )
    (net (code "15") (name "I2C_PW") (class "Default")
      (node (ref "C1") (pin "1") (pinfunction "1_1") (pintype "passive"))
      (node (ref "C2") (pin "1") (pinfunction "1_1") (pintype "passive"))
      (node (ref "R1_PINH") (pin "2") (pinfunction "2_2") (pintype "passive"))
      (node (ref "R2-PINH") (pin "2") (pinfunction "2_2") (pintype "passive"))
      (node (ref "SENSOR2") (pin "2") (pinfunction "CSB_2") (pintype "input"))
      (node (ref "SENSOR2") (pin "6") (pinfunction "VDDIO_6") (pintype "power_in"))
      (node (ref "SENSOR2") (pin "8") (pinfunction "VDD_8") (pintype "power_in"))
      (node (ref "U2") (pin "17") (pinfunction "IO19_17") (pintype "bidirectional"))
    )
    (net (code "16") (name "INT_RTC") (class "Default")
      (node (ref "R1_PINH1") (pin "1") (pinfunction "1_1") (pintype "passive"))
      (node (ref "TP15") (pin "TP") (pinfunction "TP_TP") (pintype "input"))
      (node (ref "U2") (pin "8") (pinfunction "IO0_8") (pintype "bidirectional"))
      (node (ref "U3") (pin "3") (pinfunction "SQW/~{INT}_3") (pintype "output"))
    )
    (net (code "17") (name "IO{slash}BOOT") (class "Default")
      (node (ref "BOOT_BUTTON") (pin "3") (pinfunction "3_3") (pintype "passive"))
      (node (ref "BOOT_BUTTON") (pin "4") (pinfunction "4_4") (pintype "passive"))
      (node (ref "C6") (pin "1") (pinfunction "1_1") (pintype "passive"))
      (node (ref "R_BOOT") (pin "1") (pinfunction "1_1") (pintype "passive"))
      (node (ref "U2") (pin "15") (pinfunction "IO9_15") (pintype "bidirectional"))
    )
    (net (code "18") (name "IO{slash}CHANGE") (class "Default")
      (node (ref "C10") (pin "1") (pinfunction "1_1") (pintype "passive"))
      (node (ref "CHANGE_BUTTON") (pin "3") (pinfunction "3_3") (pintype "passive"))
      (node (ref "CHANGE_BUTTON") (pin "4") (pinfunction "4_4") (pintype "passive"))
      (node (ref "R_CHANGE") (pin "1") (pinfunction "1_1") (pintype "passive"))
      (node (ref "U2") (pin "23") (pinfunction "IO15_23") (pintype "bidirectional"))
    )
    (net (code "19") (name "MISO") (class "Default")
      (node (ref "D12") (pin "2") (pinfunction "2_2") (pintype "passive"))
      (node (ref "J4") (pin "P7") (pinfunction "DAT0_P7") (pintype "bidirectional"))
      (node (ref "R8") (pin "1") (pinfunction "1_1") (pintype "passive"))
      (node (ref "TP6") (pin "TP") (pinfunction "TP_TP") (pintype "input"))
      (node (ref "U1") (pin "2") (pinfunction "DO(IO1)_2") (pintype "bidirectional"))
      (node (ref "U2") (pin "27") (pinfunction "IO2_27") (pintype "bidirectional"))
    )
    (net (code "20") (name "MOSI") (class "Default")
      (node (ref "D11") (pin "2") (pinfunction "2_2") (pintype "passive"))
      (node (ref "J1") (pin "14") (pinfunction "14_14") (pintype "bidirectional"))
      (node (ref "J4") (pin "P3") (pinfunction "CMD_P3") (pintype "bidirectional"))
      (node (ref "R7") (pin "1") (pinfunction "1_1") (pintype "passive"))
      (node (ref "TP7") (pin "TP") (pinfunction "TP_TP") (pintype "input"))
      (node (ref "U1") (pin "5") (pinfunction "DI(IO0)_5") (pintype "bidirectional"))
      (node (ref "U2") (pin "7") (pinfunction "IO7_7") (pintype "bidirectional"))
    )
    (net (code "21") (name "N$12") (class "Default")
      (node (ref "D2") (pin "2") (pinfunction "ANODE_2") (pintype "bidirectional"))
      (node (ref "Q1") (pin "1") (pinfunction "G_1") (pintype "bidirectional"))
      (node (ref "R1_PWRUSB") (pin "2") (pinfunction "2_2") (pintype "passive"))
    )
    (net (code "22") (name "Net-(CHG_LED-PadC)") (class "Default")
      (node (ref "CHG_LED") (pin "C") (pinfunction "C_C") (pintype "passive"))
      (node (ref "R1_BAT") (pin "1") (pinfunction "1_1") (pintype "passive"))
    )
    (net (code "23") (name "Net-(D2-CATHODE)") (class "Default")
      (node (ref "C1_BAT1") (pin "1") (pinfunction "1_1") (pintype "passive"))
      (node (ref "D2") (pin "1") (pinfunction "CATHODE_1") (pintype "bidirectional"))
      (node (ref "IC4") (pin "1") (pinfunction "VIN_1") (pintype "bidirectional"))
      (node (ref "IC4") (pin "3") (pinfunction "CE_3") (pintype "bidirectional"))
      (node (ref "Q1") (pin "2") (pinfunction "S_2") (pintype "bidirectional"))
    )
    (net (code "24") (name "Net-(D3-A)") (class "Default")
      (node (ref "C4") (pin "1") (pinfunction "1_1") (pintype "passive"))
      (node (ref "D3") (pin "2") (pinfunction "A_2") (pintype "bidirectional"))
      (node (ref "D4") (pin "1") (pinfunction "K_1") (pintype "bidirectional"))
    )
    (net (code "25") (name "Net-(D7-CATHODE)") (class "Default")
      (node (ref "D7") (pin "1") (pinfunction "CATHODE_1") (pintype "bidirectional"))
      (node (ref "R_CAPACITOR") (pin "1") (pinfunction "1_1") (pintype "passive"))
    )
    (net (code "26") (name "Net-(EPD_C1-Pad2)") (class "Default")
      (node (ref "EPD_C1") (pin "2") (pinfunction "2_2") (pintype "passive"))
      (node (ref "J1") (pin "4") (pinfunction "4_4") (pintype "bidirectional"))
    )
    (net (code "27") (name "Net-(EPD_C2-Pad2)") (class "Default")
      (node (ref "EPD_C2") (pin "2") (pinfunction "2_2") (pintype "passive"))
      (node (ref "J1") (pin "5") (pinfunction "5_5") (pintype "bidirectional"))
    )
    (net (code "28") (name "Net-(EPD_C6-Pad2)") (class "Default")
      (node (ref "EPD_C6") (pin "2") (pinfunction "2_2") (pintype "passive"))
      (node (ref "J1") (pin "18") (pinfunction "18_18") (pintype "bidirectional"))
    )
    (net (code "29") (name "Net-(EPD_C7-Pad2)") (class "Default")
      (node (ref "EPD_C7") (pin "2") (pinfunction "2_2") (pintype "passive"))
      (node (ref "J1") (pin "19") (pinfunction "19_19") (pintype "bidirectional"))
    )
    (net (code "30") (name "Net-(EPD_C8-Pad2)") (class "Default")
      (node (ref "EPD_C8") (pin "2") (pinfunction "2_2") (pintype "passive"))
      (node (ref "J1") (pin "20") (pinfunction "20_20") (pintype "bidirectional"))
    )
    (net (code "31") (name "Net-(EPD_C10-Pad2)") (class "Default")
      (node (ref "EPD_C10") (pin "2") (pinfunction "2_2") (pintype "passive"))
      (node (ref "J1") (pin "22") (pinfunction "22_22") (pintype "bidirectional"))
    )
    (net (code "32") (name "Net-(EPD_C12-Pad2)") (class "Default")
      (node (ref "EPD_C12") (pin "2") (pinfunction "2_2") (pintype "passive"))
      (node (ref "J1") (pin "24") (pinfunction "24_24") (pintype "bidirectional"))
    )
    (net (code "33") (name "Net-(IC1-CT)") (class "Default")
      (node (ref "C_DELAY") (pin "1") (pinfunction "1_1") (pintype "passive"))
      (node (ref "IC1") (pin "5") (pinfunction "CT_5") (pintype "bidirectional"))
    )
    (net (code "34") (name "Net-(J2-PadA5)") (class "Default")
      (node (ref "J2") (pin "A5") (pinfunction "A5_A5") (pintype "bidirectional"))
      (node (ref "R2-USB1") (pin "2") (pinfunction "2_2") (pintype "passive"))
    )
    (net (code "35") (name "Net-(J2-PadB5)") (class "Default")
      (node (ref "J2") (pin "B5") (pinfunction "B5_B5") (pintype "bidirectional"))
      (node (ref "R2-USB") (pin "1") (pinfunction "1_1") (pintype "passive"))
    )
    (net (code "36") (name "Net-(MCP73831-PROG)") (class "Default")
      (node (ref "MCP73831") (pin "5") (pinfunction "PROG_5") (pintype "input"))
      (node (ref "R2_BAT") (pin "2") (pinfunction "2_2") (pintype "passive"))
    )
    (net (code "37") (name "Net-(MCP73831-STAT)") (class "Default")
      (node (ref "MCP73831") (pin "1") (pinfunction "STAT_1") (pintype "output"))
      (node (ref "R1_BAT") (pin "2") (pinfunction "2_2") (pintype "passive"))
    )
    (net (code "38") (name "PREVGH") (class "Default")
      (node (ref "D5") (pin "1") (pinfunction "K_1") (pintype "bidirectional"))
      (node (ref "EPD_C9") (pin "2") (pinfunction "2_2") (pintype "passive"))
      (node (ref "J1") (pin "21") (pinfunction "21_21") (pintype "bidirectional"))
    )
    (net (code "39") (name "PREVGL") (class "Default")
      (node (ref "D4") (pin "2") (pinfunction "A_2") (pintype "bidirectional"))
      (node (ref "EPD_C11") (pin "2") (pinfunction "2_2") (pintype "passive"))
      (node (ref "J1") (pin "23") (pinfunction "23_23") (pintype "bidirectional"))
    )
    (net (code "40") (name "RESE") (class "Default")
      (node (ref "J1") (pin "3") (pinfunction "3_3") (pintype "bidirectional"))
      (node (ref "Q3") (pin "2") (pinfunction "S_2") (pintype "bidirectional"))
      (node (ref "R3") (pin "2") (pinfunction "2_2") (pintype "passive"))
    )
    (net (code "41") (name "RESE'") (class "Default")
      (node (ref "R2") (pin "2") (pinfunction "2_2") (pintype "passive"))
      (node (ref "R3") (pin "1") (pinfunction "1_1") (pintype "passive"))
      (node (ref "SJ1") (pin "2") (pinfunction "2_2") (pintype "passive"))
    )
    (net (code "42") (name "RESET") (class "Default")
      (node (ref "C5") (pin "1") (pinfunction "1_1") (pintype "passive"))
      (node (ref "IC1") (pin "1") (pinfunction "VOUT_1") (pintype "bidirectional"))
      (node (ref "RESET_BUTTON") (pin "3") (pinfunction "3_3") (pintype "passive"))
      (node (ref "RESET_BUTTON") (pin "4") (pinfunction "4_4") (pintype "passive"))
      (node (ref "R_RESET") (pin "1") (pinfunction "1_1") (pintype "passive"))
      (node (ref "U2") (pin "3") (pinfunction "EN_3") (pintype "input"))
    )
    (net (code "43") (name "RTC_RST") (class "Default")
      (node (ref "U2") (pin "16") (pinfunction "IO18_16") (pintype "bidirectional"))
      (node (ref "U3") (pin "4") (pinfunction "~{RST}_4") (pintype "input"))
    )
    (net (code "44") (name "RX") (class "Default")
      (node (ref "TP2") (pin "TP") (pinfunction "TP_TP") (pintype "input"))
      (node (ref "U2") (pin "24") (pinfunction "RXD0/GPIO17_24") (pintype "bidirectional"))
    )
    (net (code "45") (name "SCK") (class "Default")
      (node (ref "D10") (pin "2") (pinfunction "2_2") (pintype "passive"))
      (node (ref "J1") (pin "13") (pinfunction "13_13") (pintype "bidirectional"))
      (node (ref "J4") (pin "P5") (pinfunction "CLK_P5") (pintype "bidirectional"))
      (node (ref "R6") (pin "1") (pinfunction "1_1") (pintype "passive"))
      (node (ref "TP8") (pin "TP") (pinfunction "TP_TP") (pintype "input"))
      (node (ref "U1") (pin "6") (pinfunction "CLK_6") (pintype "input"))
      (node (ref "U2") (pin "6") (pinfunction "IO6_6") (pintype "bidirectional"))
    )
    (net (code "46") (name "SCL") (class "Default")
      (node (ref "J3") (pin "4") (pinfunction "4_4") (pintype "passive"))
      (node (ref "R2-PINH") (pin "1") (pinfunction "1_1") (pintype "passive"))
      (node (ref "SENSOR2") (pin "4") (pinfunction "SCK_4") (pintype "input"))
      (node (ref "U2") (pin "20") (pinfunction "IO22_20") (pintype "bidirectional"))
      (node (ref "U3") (pin "16") (pinfunction "SCL_16") (pintype "input"))
      (node (ref "U4") (pin "7") (pinfunction "SCL_7") (pintype "input"))
    )
    (net (code "47") (name "SDA") (class "Default")
      (node (ref "J3") (pin "3") (pinfunction "3_3") (pintype "passive"))
      (node (ref "R1_PINH") (pin "1") (pinfunction "1_1") (pintype "passive"))
      (node (ref "SENSOR2") (pin "3") (pinfunction "SDI_3") (pintype "bidirectional"))
      (node (ref "U2") (pin "19") (pinfunction "IO21_19") (pintype "bidirectional"))
      (node (ref "U3") (pin "15") (pinfunction "SDA_15") (pintype "bidirectional"))
      (node (ref "U4") (pin "8") (pinfunction "SDA_8") (pintype "bidirectional"))
    )
    (net (code "48") (name "SRC") (class "Default")
      (node (ref "C4") (pin "2") (pinfunction "2_2") (pintype "passive"))
      (node (ref "D5") (pin "2") (pinfunction "A_2") (pintype "bidirectional"))
      (node (ref "L1") (pin "1") (pinfunction "1_1") (pintype "passive"))
      (node (ref "Q3") (pin "3") (pinfunction "D_3") (pintype "bidirectional"))
    )
    (net (code "49") (name "SS_SD") (class "Default")
      (node (ref "D8") (pin "2") (pinfunction "2_2") (pintype "passive"))
      (node (ref "J4") (pin "P2") (pinfunction "CD/DAT3_P2") (pintype "bidirectional"))
      (node (ref "R10") (pin "1") (pinfunction "1_1") (pintype "passive"))
      (node (ref "U2") (pin "4") (pinfunction "IO4_4") (pintype "bidirectional"))
    )
    (net (code "50") (name "TX") (class "Default")
      (node (ref "TP1") (pin "TP") (pinfunction "TP_TP") (pintype "input"))
      (node (ref "U2") (pin "25") (pinfunction "TXD0/GPIO16_25") (pintype "bidirectional"))
    )
    (net (code "51") (name "USB_D+") (class "Default")
      (node (ref "D1") (pin "1") (pinfunction "I/O1_1_1") (pintype "bidirectional"))
      (node (ref "U2") (pin "14") (pinfunction "IO13_14") (pintype "bidirectional"))
    )
    (net (code "52") (name "USB_D-") (class "Default")
      (node (ref "D1") (pin "3") (pinfunction "I/O2_1_3") (pintype "bidirectional"))
      (node (ref "U2") (pin "13") (pinfunction "IO12_13") (pintype "bidirectional"))
    )
    (net (code "53") (name "VBAT") (class "Default")
      (node (ref "C2_BAT") (pin "1") (pinfunction "1_1") (pintype "passive"))
      (node (ref "MCP73831") (pin "3") (pinfunction "VBAT_3") (pintype "power_in"))
      (node (ref "Q1") (pin "3") (pinfunction "D_3") (pintype "bidirectional"))
      (node (ref "TP3") (pin "TP") (pinfunction "TP_TP") (pintype "input"))
      (node (ref "U4") (pin "2") (pinfunction "CELL_2") (pintype "power_in"))
      (node (ref "U4") (pin "3") (pinfunction "VDD_3") (pintype "power_in"))
    )
    (net (code "54") (name "VBUS") (class "Default")
      (node (ref "C1_BAT") (pin "1") (pinfunction "1_1") (pintype "passive"))
      (node (ref "C4_USB") (pin "1") (pinfunction "1_1") (pintype "passive"))
      (node (ref "C5_USB") (pin "1") (pinfunction "1_1") (pintype "passive"))
      (node (ref "CHG_LED") (pin "A") (pinfunction "A_A") (pintype "passive"))
      (node (ref "D1") (pin "5") (pinfunction "VBUS_5") (pintype "bidirectional"))
      (node (ref "MCP73831") (pin "4") (pinfunction "VIN_4") (pintype "power_in"))
      (node (ref "PFMF.050.1") (pin "2") (pinfunction "2_2") (pintype "passive"))
      (node (ref "TP14") (pin "TP") (pinfunction "TP_TP") (pintype "input"))
    )
    (net (code "55") (name "VRTC") (class "Default")
      (node (ref "C10_SUPERCAP") (pin "1") (pinfunction "1_1") (pintype "passive"))
      (node (ref "C8") (pin "1") (pinfunction "1_1") (pintype "passive"))
      (node (ref "R_CAPACITOR") (pin "2") (pinfunction "2_2") (pintype "passive"))
      (node (ref "U3") (pin "14") (pinfunction "VBAT_14") (pintype "power_in"))
    )
    (net (code "56") (name "VUSB") (class "Default")
      (node (ref "J2") (pin "A4") (pinfunction "A4_A4") (pintype "bidirectional"))
      (node (ref "J2") (pin "A9") (pinfunction "A9_A9") (pintype "bidirectional"))
      (node (ref "J2") (pin "B4") (pinfunction "B4_B4") (pintype "bidirectional"))
      (node (ref "J2") (pin "B9") (pinfunction "B9_B9") (pintype "bidirectional"))
      (node (ref "PFMF.050.1") (pin "1") (pinfunction "1_1") (pintype "passive"))
    )
    (net (code "57") (name "unconnected-(IC1-NC-Pad4)") (class "Default")
      (node (ref "IC1") (pin "4") (pinfunction "NC_4") (pintype "no_connect"))
    )
    (net (code "58") (name "unconnected-(IC4-NC-Pad4)") (class "Default")
      (node (ref "IC4") (pin "4") (pinfunction "NC_4") (pintype "no_connect"))
    )
    (net (code "59") (name "unconnected-(J1-Pad1)") (class "Default")
      (node (ref "J1") (pin "1") (pinfunction "1_1") (pintype "bidirectional"))
    )
    (net (code "60") (name "unconnected-(J1-Pad6)") (class "Default")
      (node (ref "J1") (pin "6") (pinfunction "6_6") (pintype "bidirectional"))
    )
    (net (code "61") (name "unconnected-(J1-Pad7)") (class "Default")
      (node (ref "J1") (pin "7") (pinfunction "7_7") (pintype "bidirectional"))
    )
    (net (code "62") (name "unconnected-(J2-PadA8)") (class "Default")
      (node (ref "J2") (pin "A8") (pinfunction "A8_A8") (pintype "bidirectional"))
    )
    (net (code "63") (name "unconnected-(J2-PadB8)") (class "Default")
      (node (ref "J2") (pin "B8") (pinfunction "B8_B8") (pintype "bidirectional"))
    )
    (net (code "64") (name "unconnected-(J4-DAT1-PadP8)") (class "Default")
      (node (ref "J4") (pin "P8") (pinfunction "DAT1_P8") (pintype "bidirectional"))
    )
    (net (code "65") (name "unconnected-(J4-DAT2-PadP1)") (class "Default")
      (node (ref "J4") (pin "P1") (pinfunction "DAT2_P1") (pintype "bidirectional"))
    )
    (net (code "66") (name "unconnected-(J4-DETECTION_1-PadS1)") (class "Default")
      (node (ref "J4") (pin "S1") (pinfunction "DETECTION_1_S1") (pintype "bidirectional"))
    )
    (net (code "67") (name "unconnected-(J4-DETECTION_2-PadS2)") (class "Default")
      (node (ref "J4") (pin "S2") (pinfunction "DETECTION_2_S2") (pintype "bidirectional"))
    )
    (net (code "68") (name "unconnected-(U2-NC-Pad22)") (class "Default")
      (node (ref "U2") (pin "22") (pinfunction "NC_22") (pintype "no_connect"))
    )
    (net (code "69") (name "unconnected-(U4-~{ALERT}-Pad5)") (class "Default")
      (node (ref "U4") (pin "5") (pinfunction "~{ALERT}_5") (pintype "output"))
    )
  )
)
